# PI_R3_REV1_LED.net
KiCad netlist of a schematic drawn in Altium Designer
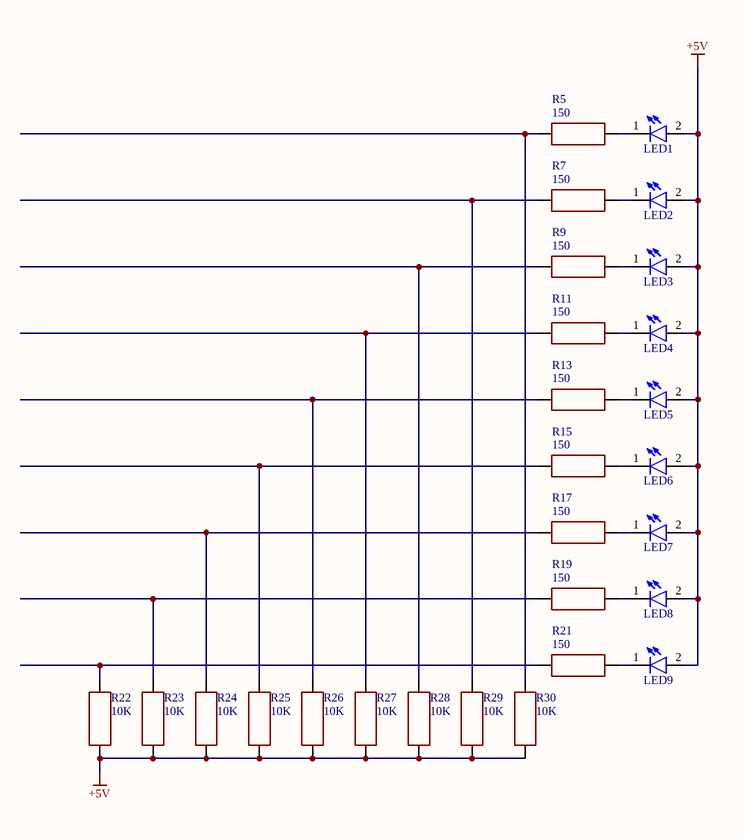
[diagram p0: PI_R3_REV1_LED.SchDoc]

(export (version "E")
  (design (tool "Eeschema 10.0.6"))
  (components
    (comp (ref "LED1")
      (value "L1043")
      (footprint "L1043")
      (fields (field (name "MANUFACTURER") "Kingbright"))
      (libsource (lib "MY_INT_LIB") (part "L1043"))
    )
    (comp (ref "LED2")
      (value "L1043")
      (footprint "L1043")
      (fields (field (name "MANUFACTURER") "Kingbright"))
      (libsource (lib "MY_INT_LIB") (part "L1043"))
    )
    (comp (ref "LED3")
      (value "L1043")
      (footprint "L1043")
      (fields (field (name "MANUFACTURER") "Kingbright"))
      (libsource (lib "MY_INT_LIB") (part "L1043"))
    )
    (comp (ref "LED4")
      (value "L1043")
      (footprint "L1043")
      (fields (field (name "MANUFACTURER") "Kingbright"))
      (libsource (lib "MY_INT_LIB") (part "L1043"))
    )
    (comp (ref "LED5")
      (value "L1043")
      (footprint "L1043")
      (fields (field (name "MANUFACTURER") "Kingbright"))
      (libsource (lib "MY_INT_LIB") (part "L1043"))
    )
    (comp (ref "LED6")
      (value "L1043")
      (footprint "L1043")
      (fields (field (name "MANUFACTURER") "Kingbright"))
      (libsource (lib "MY_INT_LIB") (part "L1043"))
    )
    (comp (ref "LED7")
      (value "L1043")
      (footprint "L1043")
      (fields (field (name "MANUFACTURER") "Kingbright"))
      (libsource (lib "MY_INT_LIB") (part "L1043"))
    )
    (comp (ref "LED8")
      (value "L1043")
      (footprint "L1043")
      (fields (field (name "MANUFACTURER") "Kingbright"))
      (libsource (lib "MY_INT_LIB") (part "L1043"))
    )
    (comp (ref "LED9")
      (value "L1043")
      (footprint "L1043")
      (fields (field (name "MANUFACTURER") "Kingbright"))
      (libsource (lib "MY_INT_LIB") (part "L1043"))
    )
    (comp (ref "R5")
      (value "150")
      (footprint "RES: 0402")
      (fields (field (name "TOLERANCE") "±5%"))
      (libsource (lib "resistor") (part "Resistor_0402"))
    )
    (comp (ref "R7")
      (value "150")
      (footprint "RES: 0402")
      (fields (field (name "TOLERANCE") "±5%"))
      (libsource (lib "resistor") (part "Resistor_0402"))
    )
    (comp (ref "R9")
      (value "150")
      (footprint "RES: 0402")
      (fields (field (name "TOLERANCE") "±5%"))
      (libsource (lib "resistor") (part "Resistor_0402"))
    )
    (comp (ref "R11")
      (value "150")
      (footprint "RES: 0402")
      (fields (field (name "TOLERANCE") "±5%"))
      (libsource (lib "resistor") (part "Resistor_0402"))
    )
    (comp (ref "R13")
      (value "150")
      (footprint "RES: 0402")
      (fields (field (name "TOLERANCE") "±5%"))
      (libsource (lib "resistor") (part "Resistor_0402"))
    )
    (comp (ref "R15")
      (value "150")
      (footprint "RES: 0402")
      (fields (field (name "TOLERANCE") "±5%"))
      (libsource (lib "resistor") (part "Resistor_0402"))
    )
    (comp (ref "R17")
      (value "150")
      (footprint "RES: 0402")
      (fields (field (name "TOLERANCE") "±5%"))
      (libsource (lib "resistor") (part "Resistor_0402"))
    )
    (comp (ref "R19")
      (value "150")
      (footprint "RES: 0402")
      (fields (field (name "TOLERANCE") "±5%"))
      (libsource (lib "resistor") (part "Resistor_0402"))
    )
    (comp (ref "R21")
      (value "150")
      (footprint "RES: 0402")
      (fields (field (name "TOLERANCE") "±5%"))
      (libsource (lib "resistor") (part "Resistor_0402"))
    )
    (comp (ref "R22")
      (value "10K")
      (footprint "RES: 0402")
      (fields (field (name "TOLERANCE") "±5%"))
      (libsource (lib "") (part "Resistor_0402_1"))
    )
    (comp (ref "R23")
      (value "10K")
      (footprint "RES: 0402")
      (fields (field (name "TOLERANCE") "±5%"))
      (libsource (lib "") (part "Resistor_0402_1"))
    )
    (comp (ref "R24")
      (value "10K")
      (footprint "RES: 0402")
      (fields (field (name "TOLERANCE") "±5%"))
      (libsource (lib "") (part "Resistor_0402_1"))
    )
    (comp (ref "R25")
      (value "10K")
      (footprint "RES: 0402")
      (fields (field (name "TOLERANCE") "±5%"))
      (libsource (lib "") (part "Resistor_0402_1"))
    )
    (comp (ref "R26")
      (value "10K")
      (footprint "RES: 0402")
      (fields (field (name "TOLERANCE") "±5%"))
      (libsource (lib "") (part "Resistor_0402_1"))
    )
    (comp (ref "R27")
      (value "10K")
      (footprint "RES: 0402")
      (fields (field (name "TOLERANCE") "±5%"))
      (libsource (lib "") (part "Resistor_0402_1"))
    )
    (comp (ref "R28")
      (value "10K")
      (footprint "RES: 0402")
      (fields (field (name "TOLERANCE") "±5%"))
      (libsource (lib "") (part "Resistor_0402_1"))
    )
    (comp (ref "R29")
      (value "10K")
      (footprint "RES: 0402")
      (fields (field (name "TOLERANCE") "±5%"))
      (libsource (lib "") (part "Resistor_0402_1"))
    )
    (comp (ref "R30")
      (value "10K")
      (footprint "RES: 0402")
      (fields (field (name "TOLERANCE") "±5%"))
      (libsource (lib "") (part "Resistor_0402_1"))
    )
  )
  (nets
    (net (code "1") (name "+5V") (class "Default")
      (node (ref "LED1") (pin "2") (pintype "passive"))
      (node (ref "LED2") (pin "2") (pintype "passive"))
      (node (ref "LED3") (pin "2") (pintype "passive"))
      (node (ref "LED4") (pin "2") (pintype "passive"))
      (node (ref "LED5") (pin "2") (pintype "passive"))
      (node (ref "LED6") (pin "2") (pintype "passive"))
      (node (ref "LED7") (pin "2") (pintype "passive"))
      (node (ref "LED8") (pin "2") (pintype "passive"))
      (node (ref "LED9") (pin "2") (pintype "passive"))
      (node (ref "R22") (pin "2") (pinfunction "2_2") (pintype "passive"))
      (node (ref "R23") (pin "2") (pinfunction "2_2") (pintype "passive"))
      (node (ref "R24") (pin "2") (pinfunction "2_2") (pintype "passive"))
      (node (ref "R25") (pin "2") (pinfunction "2_2") (pintype "passive"))
      (node (ref "R26") (pin "2") (pinfunction "2_2") (pintype "passive"))
      (node (ref "R27") (pin "2") (pinfunction "2_2") (pintype "passive"))
      (node (ref "R28") (pin "2") (pinfunction "2_2") (pintype "passive"))
      (node (ref "R29") (pin "2") (pinfunction "2_2") (pintype "passive"))
      (node (ref "R30") (pin "2") (pinfunction "2_2") (pintype "passive"))
    )
    (net (code "2") (name "Net-(LED1-Pad1)") (class "Default")
      (node (ref "LED1") (pin "1") (pintype "passive"))
      (node (ref "R5") (pin "2") (pinfunction "2_2") (pintype "passive"))
    )
    (net (code "3") (name "Net-(LED2-Pad1)") (class "Default")
      (node (ref "LED2") (pin "1") (pintype "passive"))
      (node (ref "R7") (pin "2") (pinfunction "2_2") (pintype "passive"))
    )
    (net (code "4") (name "Net-(LED3-Pad1)") (class "Default")
      (node (ref "LED3") (pin "1") (pintype "passive"))
      (node (ref "R9") (pin "2") (pinfunction "2_2") (pintype "passive"))
    )
    (net (code "5") (name "Net-(LED4-Pad1)") (class "Default")
      (node (ref "LED4") (pin "1") (pintype "passive"))
      (node (ref "R11") (pin "2") (pinfunction "2_2") (pintype "passive"))
    )
    (net (code "6") (name "Net-(LED5-Pad1)") (class "Default")
      (node (ref "LED5") (pin "1") (pintype "passive"))
      (node (ref "R13") (pin "2") (pinfunction "2_2") (pintype "passive"))
    )
    (net (code "7") (name "Net-(LED6-Pad1)") (class "Default")
      (node (ref "LED6") (pin "1") (pintype "passive"))
      (node (ref "R15") (pin "2") (pinfunction "2_2") (pintype "passive"))
    )
    (net (code "8") (name "Net-(LED7-Pad1)") (class "Default")
      (node (ref "LED7") (pin "1") (pintype "passive"))
      (node (ref "R17") (pin "2") (pinfunction "2_2") (pintype "passive"))
    )
    (net (code "9") (name "Net-(LED8-Pad1)") (class "Default")
      (node (ref "LED8") (pin "1") (pintype "passive"))
      (node (ref "R19") (pin "2") (pinfunction "2_2") (pintype "passive"))
    )
    (net (code "10") (name "Net-(LED9-Pad1)") (class "Default")
      (node (ref "LED9") (pin "1") (pintype "passive"))
      (node (ref "R21") (pin "2") (pinfunction "2_2") (pintype "passive"))
    )
    (net (code "11") (name "Net-(R11-Pad1)") (class "Default")
      (node (ref "R11") (pin "1") (pinfunction "1_1") (pintype "passive"))
      (node (ref "R27") (pin "1") (pinfunction "1_1") (pintype "passive"))
    )
    (net (code "12") (name "Net-(R13-Pad1)") (class "Default")
      (node (ref "R13") (pin "1") (pinfunction "1_1") (pintype "passive"))
      (node (ref "R26") (pin "1") (pinfunction "1_1") (pintype "passive"))
    )
    (net (code "13") (name "Net-(R15-Pad1)") (class "Default")
      (node (ref "R15") (pin "1") (pinfunction "1_1") (pintype "passive"))
      (node (ref "R25") (pin "1") (pinfunction "1_1") (pintype "passive"))
    )
    (net (code "14") (name "Net-(R17-Pad1)") (class "Default")
      (node (ref "R17") (pin "1") (pinfunction "1_1") (pintype "passive"))
      (node (ref "R24") (pin "1") (pinfunction "1_1") (pintype "passive"))
    )
    (net (code "15") (name "Net-(R19-Pad1)") (class "Default")
      (node (ref "R19") (pin "1") (pinfunction "1_1") (pintype "passive"))
      (node (ref "R23") (pin "1") (pinfunction "1_1") (pintype "passive"))
    )
    (net (code "16") (name "Net-(R21-Pad1)") (class "Default")
      (node (ref "R21") (pin "1") (pinfunction "1_1") (pintype "passive"))
      (node (ref "R22") (pin "1") (pinfunction "1_1") (pintype "passive"))
    )
    (net (code "17") (name "Net-(R28-Pad1)") (class "Default")
      (node (ref "R28") (pin "1") (pinfunction "1_1") (pintype "passive"))
      (node (ref "R9") (pin "1") (pinfunction "1_1") (pintype "passive"))
    )
    (net (code "18") (name "Net-(R29-Pad1)") (class "Default")
      (node (ref "R29") (pin "1") (pinfunction "1_1") (pintype "passive"))
      (node (ref "R7") (pin "1") (pinfunction "1_1") (pintype "passive"))
    )
    (net (code "19") (name "Net-(R30-Pad1)") (class "Default")
      (node (ref "R30") (pin "1") (pinfunction "1_1") (pintype "passive"))
      (node (ref "R5") (pin "1") (pinfunction "1_1") (pintype "passive"))
    )
  )
)
